# USB_OTG_FS.net
KiCad netlist of a schematic drawn in Altium Designer
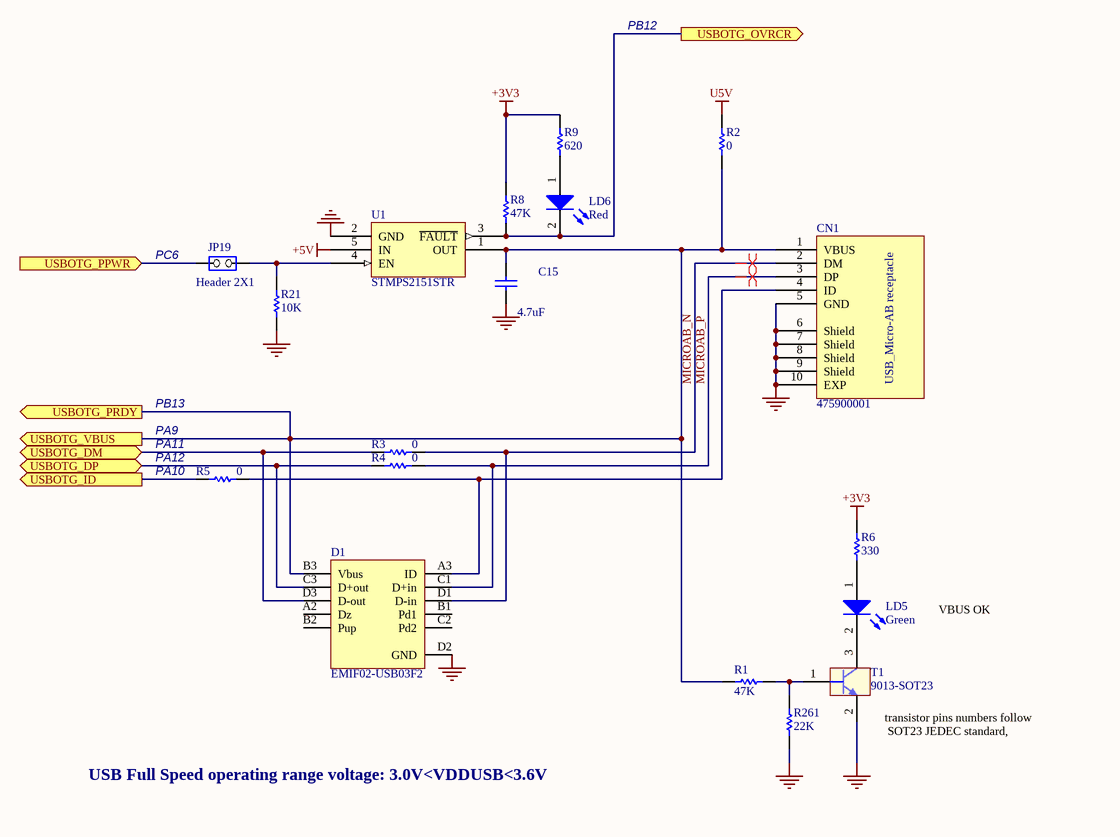
[diagram p0: USB_OTG_FS.SchDoc]

(export (version "E")
  (design (tool "Eeschema 10.0.6"))
  (components
    (comp (ref "C15")
      (value "4.7uF")
      (footprint "0603C")
      (description "Capacitor")
      (fields (field (name "PUBLISHER") "Altium Limited"))
      (libsource (lib "Miscellaneous Devices") (part "CAP"))
    )
    (comp (ref "CN1")
      (value "475900001")
      (footprint "MOLEX_47590001")
      (libsource (lib "mb1045") (part "475900001"))
    )
    (comp (ref "D1")
      (value "EMIF02-USB03F2")
      (footprint "BGA11_0R5_1R57X2R07")
      (libsource (lib "mb1045") (part "EMIF02-USB03F2"))
    )
    (comp (ref "JP19") (value "Header 2X1") (footprint "SIP2") (libsource (lib "*") (part "JP2")))
    (comp (ref "LD5")
      (value "Green")
      (footprint "0603D")
      (description "Typical RED, GREEN, YELLOW, AMBER GaAs LED")
      (fields (field (name "PUBLISHER") "Altium Limited"))
      (libsource (lib "Miscellaneous Devices") (part "LED2"))
    )
    (comp (ref "LD6")
      (value "Red")
      (footprint "0603D")
      (description "Typical RED, GREEN, YELLOW, AMBER GaAs LED")
      (fields (field (name "PUBLISHER") "Altium Limited"))
      (libsource (lib "Miscellaneous Devices") (part "LED2"))
    )
    (comp (ref "R1")
      (value "47K")
      (footprint "0402R")
      (description "Resistor")
      (fields (field (name "PUBLISHER") "Altium Limited"))
      (libsource (lib "Miscellaneous Devices") (part "res1"))
    )
    (comp (ref "R2")
      (value "0")
      (footprint "0603R")
      (description "Resistor")
      (fields (field (name "PUBLISHER") "Altium Limited"))
      (libsource (lib "Miscellaneous Devices") (part "Res1"))
    )
    (comp (ref "R3")
      (value "0")
      (footprint "0603R")
      (description "Resistor")
      (fields (field (name "PUBLISHER") "Altium Limited"))
      (libsource (lib "Miscellaneous Devices") (part "Res1"))
    )
    (comp (ref "R4")
      (value "0")
      (footprint "0603R")
      (description "Resistor")
      (fields (field (name "PUBLISHER") "Altium Limited"))
      (libsource (lib "Miscellaneous Devices") (part "Res1"))
    )
    (comp (ref "R5")
      (value "0")
      (footprint "0603R")
      (description "Resistor")
      (fields (field (name "PUBLISHER") "Altium Limited"))
      (libsource (lib "Miscellaneous Devices") (part "Res1"))
    )
    (comp (ref "R6")
      (value "330")
      (footprint "0402R")
      (description "Resistor")
      (fields (field (name "PUBLISHER") "Altium Limited"))
      (libsource (lib "Miscellaneous Devices") (part "res1"))
    )
    (comp (ref "R8")
      (value "47K")
      (footprint "0402R")
      (description "Resistor")
      (fields (field (name "PUBLISHER") "Altium Limited"))
      (libsource (lib "Miscellaneous Devices") (part "res1"))
    )
    (comp (ref "R9")
      (value "620")
      (footprint "0402R")
      (description "Resistor")
      (fields (field (name "PUBLISHER") "Altium Limited"))
      (libsource (lib "Miscellaneous Devices") (part "res1"))
    )
    (comp (ref "R21")
      (value "10K")
      (footprint "0402R")
      (description "Resistor")
      (fields (field (name "PUBLISHER") "Altium Limited"))
      (libsource (lib "Miscellaneous Devices") (part "Res1"))
    )
    (comp (ref "R261")
      (value "22K")
      (footprint "0402R")
      (description "Resistor")
      (fields (field (name "PUBLISHER") "Altium Limited"))
      (libsource (lib "Miscellaneous Devices") (part "res1"))
    )
    (comp (ref "T1")
      (value "9013-SOT23")
      (footprint "SOT-23")
      (description "NPN Bipolar Transistor, SOT-23 Footprint")
      (libsource (lib "MCD_TOOLS") (part "9013-SOT23"))
    )
    (comp (ref "U1")
      (value "STMPS2151STR")
      (footprint "SOT23-5")
      (libsource (lib "mb1045") (part "STMPS2141STR"))
    )
  )
  (nets
    (net (code "1") (name "+3V3") (class "Default")
      (node (ref "R6") (pin "1") (pinfunction "1_1") (pintype "passive"))
      (node (ref "R8") (pin "1") (pinfunction "1_1") (pintype "passive"))
      (node (ref "R9") (pin "1") (pinfunction "1_1") (pintype "passive"))
    )
    (net (code "2") (name "+5V") (class "Default")
      (node (ref "U1") (pin "5") (pinfunction "IN_5") (pintype "passive"))
    )
    (net (code "3") (name "/MICROAB_N") (class "Default")
      (node (ref "CN1") (pin "2") (pinfunction "DM_2") (pintype "passive"))
      (node (ref "D1") (pin "D1") (pinfunction "D-in_D1") (pintype "passive"))
      (node (ref "R3") (pin "1") (pinfunction "1_1") (pintype "passive"))
    )
    (net (code "4") (name "/MICROAB_P") (class "Default")
      (node (ref "CN1") (pin "3") (pinfunction "DP_3") (pintype "passive"))
      (node (ref "D1") (pin "C1") (pinfunction "D+in_C1") (pintype "passive"))
      (node (ref "R4") (pin "1") (pinfunction "1_1") (pintype "passive"))
    )
    (net (code "5") (name "/USBOTG_DM") (class "Default")
      (node (ref "D1") (pin "D3") (pinfunction "D-out_D3") (pintype "passive"))
      (node (ref "R3") (pin "2") (pinfunction "2_2") (pintype "passive"))
    )
    (net (code "6") (name "/USBOTG_DP") (class "Default")
      (node (ref "D1") (pin "C3") (pinfunction "D+out_C3") (pintype "passive"))
      (node (ref "R4") (pin "2") (pinfunction "2_2") (pintype "passive"))
    )
    (net (code "7") (name "/USBOTG_ID") (class "Default")
      (node (ref "R5") (pin "2") (pinfunction "2_2") (pintype "passive"))
    )
    (net (code "8") (name "/USBOTG_OVRCR") (class "Default")
      (node (ref "LD6") (pin "2") (pinfunction "K_2") (pintype "passive"))
      (node (ref "R8") (pin "2") (pinfunction "2_2") (pintype "passive"))
      (node (ref "U1") (pin "3") (pinfunction "~{FAULT}_3") (pintype "output"))
    )
    (net (code "9") (name "/USBOTG_PPWR") (class "Default")
      (node (ref "JP19") (pin "1") (pinfunction "COMMON_1") (pintype "passive"))
    )
    (net (code "10") (name "/USBOTG_PRDY") (class "Default")
      (node (ref "C15") (pin "1") (pinfunction "1_1") (pintype "passive"))
      (node (ref "CN1") (pin "1") (pinfunction "VBUS_1") (pintype "passive"))
      (node (ref "D1") (pin "B3") (pinfunction "Vbus_B3") (pintype "passive"))
      (node (ref "R1") (pin "1") (pinfunction "1_1") (pintype "passive"))
      (node (ref "R2") (pin "2") (pinfunction "2_2") (pintype "passive"))
      (node (ref "U1") (pin "1") (pinfunction "OUT_1") (pintype "passive"))
    )
    (net (code "11") (name "GND") (class "Default")
      (node (ref "C15") (pin "2") (pinfunction "2_2") (pintype "passive"))
      (node (ref "CN1") (pin "10") (pinfunction "EXP_10") (pintype "passive"))
      (node (ref "CN1") (pin "5") (pinfunction "GND_5") (pintype "passive"))
      (node (ref "CN1") (pin "6") (pinfunction "Shield_6") (pintype "passive"))
      (node (ref "CN1") (pin "7") (pinfunction "Shield_7") (pintype "passive"))
      (node (ref "CN1") (pin "8") (pinfunction "Shield_8") (pintype "passive"))
      (node (ref "CN1") (pin "9") (pinfunction "Shield_9") (pintype "passive"))
      (node (ref "D1") (pin "D2") (pinfunction "GND_D2") (pintype "passive"))
      (node (ref "R21") (pin "1") (pinfunction "1_1") (pintype "passive"))
      (node (ref "R261") (pin "1") (pinfunction "1_1") (pintype "passive"))
      (node (ref "T1") (pin "2") (pinfunction "E_2") (pintype "passive"))
      (node (ref "U1") (pin "2") (pinfunction "GND_2") (pintype "passive"))
    )
    (net (code "12") (name "Net-(CN1-ID)") (class "Default")
      (node (ref "CN1") (pin "4") (pinfunction "ID_4") (pintype "passive"))
      (node (ref "D1") (pin "A3") (pinfunction "ID_A3") (pintype "passive"))
      (node (ref "R5") (pin "1") (pinfunction "1_1") (pintype "passive"))
    )
    (net (code "13") (name "Net-(JP19-NO)") (class "Default")
      (node (ref "JP19") (pin "2") (pinfunction "NO_2") (pintype "passive"))
      (node (ref "R21") (pin "2") (pinfunction "2_2") (pintype "passive"))
      (node (ref "U1") (pin "4") (pinfunction "EN_4") (pintype "input"))
    )
    (net (code "14") (name "Net-(LD5-A)") (class "Default")
      (node (ref "LD5") (pin "1") (pinfunction "A_1") (pintype "passive"))
      (node (ref "R6") (pin "2") (pinfunction "2_2") (pintype "passive"))
    )
    (net (code "15") (name "Net-(LD5-K)") (class "Default")
      (node (ref "LD5") (pin "2") (pinfunction "K_2") (pintype "passive"))
      (node (ref "T1") (pin "3") (pinfunction "C_3") (pintype "passive"))
    )
    (net (code "16") (name "Net-(LD6-A)") (class "Default")
      (node (ref "LD6") (pin "1") (pinfunction "A_1") (pintype "passive"))
      (node (ref "R9") (pin "2") (pinfunction "2_2") (pintype "passive"))
    )
    (net (code "17") (name "Net-(T1-B)") (class "Default")
      (node (ref "R1") (pin "2") (pinfunction "2_2") (pintype "passive"))
      (node (ref "R261") (pin "2") (pinfunction "2_2") (pintype "passive"))
      (node (ref "T1") (pin "1") (pinfunction "B_1") (pintype "passive"))
    )
    (net (code "18") (name "U5V") (class "Default")
      (node (ref "R2") (pin "1") (pinfunction "1_1") (pintype "passive"))
    )
    (net (code "19") (name "unconnected-(D1-Dz-PadA2)") (class "Default")
      (node (ref "D1") (pin "A2") (pinfunction "Dz_A2") (pintype "passive"))
    )
    (net (code "20") (name "unconnected-(D1-Pd1-PadB1)") (class "Default")
      (node (ref "D1") (pin "B1") (pinfunction "Pd1_B1") (pintype "passive"))
    )
    (net (code "21") (name "unconnected-(D1-Pd2-PadC2)") (class "Default")
      (node (ref "D1") (pin "C2") (pinfunction "Pd2_C2") (pintype "passive"))
    )
    (net (code "22") (name "unconnected-(D1-Pup-PadB2)") (class "Default")
      (node (ref "D1") (pin "B2") (pinfunction "Pup_B2") (pintype "passive"))
    )
  )
)
